# akabeacon_circle_ble113.net
KiCad netlist of a schematic drawn in EAGLE
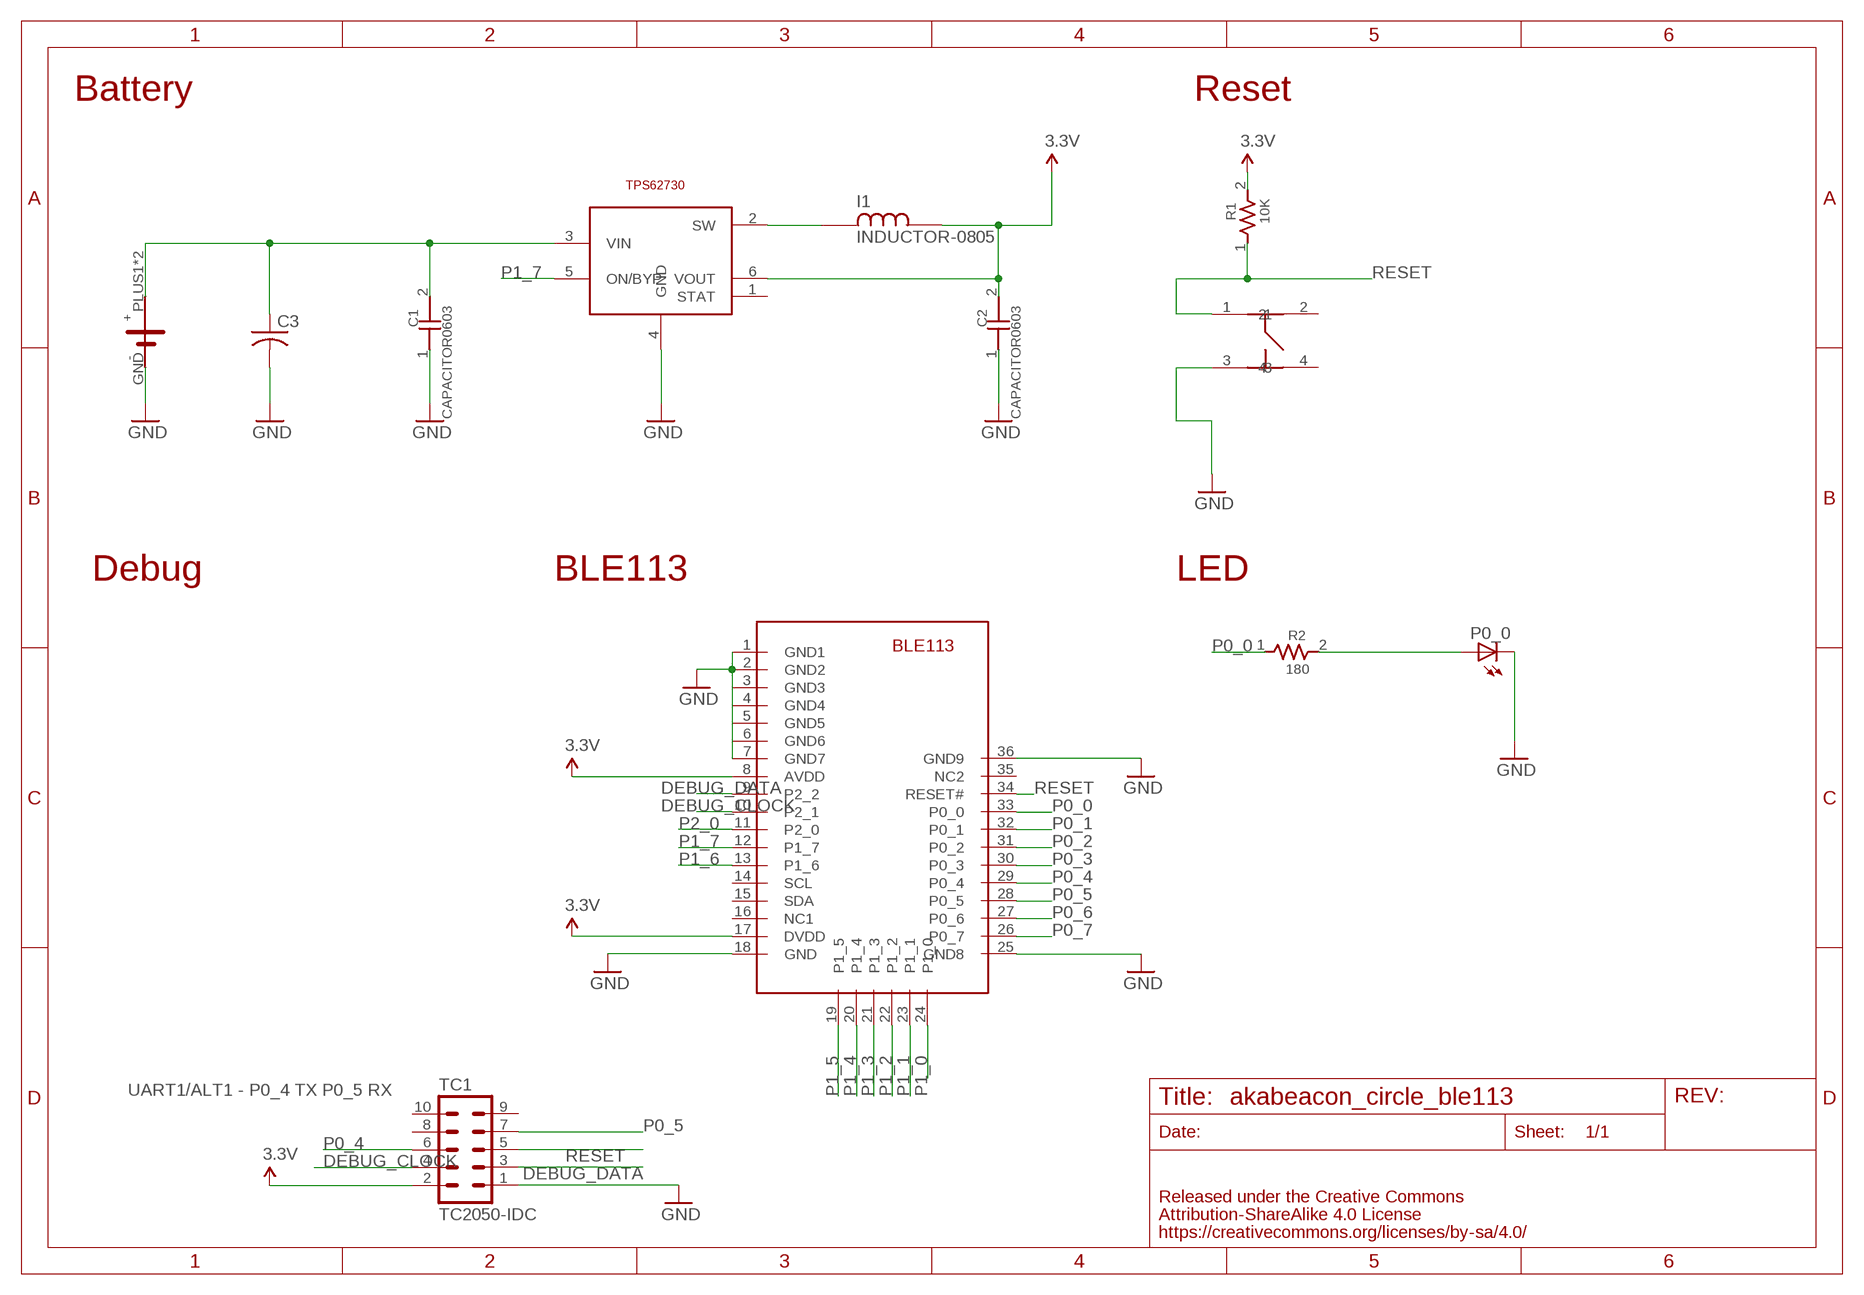
[diagram p0: schematic, sheet 1]

(export (version "E")
  (design (tool "Eeschema 10.0.6"))
  (components
    (comp (ref "C1")
      (value "CAPACITOR0603")
      (footprint "eagle-import:0603")
      (libsource (lib "eagle-import") (part "CAPACITOR0603"))
    )
    (comp (ref "C2")
      (value "CAPACITOR0603")
      (footprint "eagle-import:0603")
      (libsource (lib "eagle-import") (part "CAPACITOR0603"))
    )
    (comp (ref "C3")
      (value "C-USC3225")
      (footprint "eagle-import:C3225")
      (libsource (lib "eagle-import") (part "C-USC3225"))
    )
    (comp (ref "I1")
      (value "INDUCTOR-0805")
      (footprint "eagle-import:INDUCTOR-0805")
      (libsource (lib "eagle-import") (part "INDUCTOR-0805"))
    )
    (comp (ref "P0_0")
      (value "LEDCHIP-LED0603")
      (footprint "eagle-import:CHIP-LED0603")
      (libsource (lib "eagle-import") (part "LEDCHIP-LED0603"))
    )
    (comp (ref "R1")
      (value "10K")
      (footprint "eagle-import:0603")
      (libsource (lib "eagle-import") (part "RESISTOR0603"))
    )
    (comp (ref "R2")
      (value "180")
      (footprint "eagle-import:0603")
      (libsource (lib "eagle-import") (part "RESISTOR0603"))
    )
    (comp (ref "TC1")
      (value "TC2050-IDC")
      (footprint "eagle-import:TC2050-IDC-NL")
      (libsource (lib "eagle-import") (part "TC2050-IDC"))
    )
    (comp (ref "TPS1")
      (value "TI-TPS62730")
      (footprint "eagle-import:TI-TPS62730")
      (libsource (lib "eagle-import") (part "TI-TPS62730"))
    )
    (comp (ref "U$1")
      (value "CIRCLE-TYPE1")
      (footprint "eagle-import:CIRCLE-TYE1-TC2030")
      (libsource (lib "eagle-import") (part "CIRCLE-TYPE1"))
    )
    (comp (ref "U$4")
      (value "BLE113")
      (footprint "eagle-import:BLE113")
      (libsource (lib "eagle-import") (part "BLE113"))
    )
    (comp (ref "U$5")
      (value "SWICTH-4P(KMR2)")
      (footprint "eagle-import:SWITCH-4P(KMR2)")
      (libsource (lib "eagle-import") (part "SWICTH-4P(KMR2)"))
    )
  )
  (nets
    (net (code "1") (name "/DEBUG_CLOCK") (class "Default")
      (node (ref "TC1") (pin "4") (pinfunction "4_4") (pintype "passive"))
      (node (ref "U$4") (pin "10") (pinfunction "P2_1_10") (pintype "bidirectional"))
    )
    (net (code "2") (name "/DEBUG_DATA") (class "Default")
      (node (ref "TC1") (pin "3") (pinfunction "3_3") (pintype "passive"))
      (node (ref "U$4") (pin "9") (pinfunction "P2_2_9") (pintype "bidirectional"))
    )
    (net (code "3") (name "/P0_0") (class "Default")
      (node (ref "R2") (pin "1") (pinfunction "1_1") (pintype "passive"))
      (node (ref "U$4") (pin "33") (pinfunction "P0_0_33") (pintype "bidirectional"))
    )
    (net (code "4") (name "/P0_1") (class "Default")
      (node (ref "U$4") (pin "32") (pinfunction "P0_1_32") (pintype "bidirectional"))
    )
    (net (code "5") (name "/P0_2") (class "Default")
      (node (ref "U$4") (pin "31") (pinfunction "P0_2_31") (pintype "bidirectional"))
    )
    (net (code "6") (name "/P0_3") (class "Default")
      (node (ref "U$4") (pin "30") (pinfunction "P0_3_30") (pintype "bidirectional"))
    )
    (net (code "7") (name "/P0_4") (class "Default")
      (node (ref "TC1") (pin "6") (pinfunction "6_6") (pintype "passive"))
      (node (ref "U$4") (pin "29") (pinfunction "P0_4_29") (pintype "bidirectional"))
    )
    (net (code "8") (name "/P0_5") (class "Default")
      (node (ref "TC1") (pin "7") (pinfunction "7_7") (pintype "passive"))
      (node (ref "U$4") (pin "28") (pinfunction "P0_5_28") (pintype "bidirectional"))
    )
    (net (code "9") (name "/P0_6") (class "Default")
      (node (ref "U$4") (pin "27") (pinfunction "P0_6_27") (pintype "bidirectional"))
    )
    (net (code "10") (name "/P0_7") (class "Default")
      (node (ref "U$4") (pin "26") (pinfunction "P0_7_26") (pintype "bidirectional"))
    )
    (net (code "11") (name "/P1_0") (class "Default")
      (node (ref "U$4") (pin "24") (pinfunction "P1_0_24") (pintype "bidirectional"))
    )
    (net (code "12") (name "/P1_1") (class "Default")
      (node (ref "U$4") (pin "23") (pinfunction "P1_1_23") (pintype "bidirectional"))
    )
    (net (code "13") (name "/P1_2") (class "Default")
      (node (ref "U$4") (pin "22") (pinfunction "P1_2_22") (pintype "bidirectional"))
    )
    (net (code "14") (name "/P1_3") (class "Default")
      (node (ref "U$4") (pin "21") (pinfunction "P1_3_21") (pintype "bidirectional"))
    )
    (net (code "15") (name "/P1_4") (class "Default")
      (node (ref "U$4") (pin "20") (pinfunction "P1_4_20") (pintype "bidirectional"))
    )
    (net (code "16") (name "/P1_5") (class "Default")
      (node (ref "U$4") (pin "19") (pinfunction "P1_5_19") (pintype "bidirectional"))
    )
    (net (code "17") (name "/P1_6") (class "Default")
      (node (ref "U$4") (pin "13") (pinfunction "P1_6_13") (pintype "bidirectional"))
    )
    (net (code "18") (name "/P1_7") (class "Default")
      (node (ref "TPS1") (pin "5") (pinfunction "ON/BYP_5") (pintype "bidirectional"))
      (node (ref "U$4") (pin "12") (pinfunction "P1_7_12") (pintype "bidirectional"))
    )
    (net (code "19") (name "/P2_0") (class "Default")
      (node (ref "U$4") (pin "11") (pinfunction "P2_0_11") (pintype "bidirectional"))
    )
    (net (code "20") (name "/RESET") (class "Default")
      (node (ref "R1") (pin "1") (pinfunction "1_1") (pintype "passive"))
      (node (ref "TC1") (pin "5") (pinfunction "5_5") (pintype "passive"))
      (node (ref "U$4") (pin "34") (pinfunction "RESET#_34") (pintype "bidirectional"))
      (node (ref "U$5") (pin "1") (pinfunction "1_1") (pintype "bidirectional"))
    )
    (net (code "21") (name "3.3V") (class "Default")
      (node (ref "C2") (pin "2") (pinfunction "2_2") (pintype "passive"))
      (node (ref "I1") (pin "P$2") (pinfunction "P$2_P$2") (pintype "bidirectional"))
      (node (ref "R1") (pin "2") (pinfunction "2_2") (pintype "passive"))
      (node (ref "TC1") (pin "2") (pinfunction "2_2") (pintype "passive"))
      (node (ref "TPS1") (pin "6") (pinfunction "VOUT_6") (pintype "bidirectional"))
      (node (ref "U$4") (pin "17") (pinfunction "DVDD_17") (pintype "bidirectional"))
      (node (ref "U$4") (pin "8") (pinfunction "AVDD_8") (pintype "bidirectional"))
    )
    (net (code "22") (name "GND") (class "Default")
      (node (ref "C1") (pin "1") (pinfunction "1_1") (pintype "passive"))
      (node (ref "C2") (pin "1") (pinfunction "1_1") (pintype "passive"))
      (node (ref "C3") (pin "2") (pinfunction "2_2") (pintype "passive"))
      (node (ref "P0_0") (pin "C") (pinfunction "C_C") (pintype "passive"))
      (node (ref "TC1") (pin "1") (pinfunction "1_1") (pintype "passive"))
      (node (ref "TPS1") (pin "4") (pinfunction "GND_4") (pintype "bidirectional"))
      (node (ref "U$1") (pin "GND") (pinfunction "GND_GND") (pintype "bidirectional"))
      (node (ref "U$4") (pin "1") (pinfunction "GND1_1") (pintype "bidirectional"))
      (node (ref "U$4") (pin "18") (pinfunction "GND_18") (pintype "bidirectional"))
      (node (ref "U$4") (pin "2") (pinfunction "GND2_2") (pintype "bidirectional"))
      (node (ref "U$4") (pin "25") (pinfunction "GND8_25") (pintype "bidirectional"))
      (node (ref "U$4") (pin "3") (pinfunction "GND3_3") (pintype "bidirectional"))
      (node (ref "U$4") (pin "36") (pinfunction "GND9_36") (pintype "bidirectional"))
      (node (ref "U$4") (pin "4") (pinfunction "GND4_4") (pintype "bidirectional"))
      (node (ref "U$4") (pin "5") (pinfunction "GND5_5") (pintype "bidirectional"))
      (node (ref "U$4") (pin "6") (pinfunction "GND6_6") (pintype "bidirectional"))
      (node (ref "U$4") (pin "7") (pinfunction "GND7_7") (pintype "bidirectional"))
      (node (ref "U$5") (pin "3") (pinfunction "3_3") (pintype "bidirectional"))
    )
    (net (code "23") (name "Net-(P0_0-PadA)") (class "Default")
      (node (ref "P0_0") (pin "A") (pinfunction "A_A") (pintype "passive"))
      (node (ref "R2") (pin "2") (pinfunction "2_2") (pintype "passive"))
    )
    (net (code "24") (name "Net-(TPS1-SW)") (class "Default")
      (node (ref "I1") (pin "P$1") (pinfunction "P$1_P$1") (pintype "bidirectional"))
      (node (ref "TPS1") (pin "2") (pinfunction "SW_2") (pintype "bidirectional"))
    )
    (net (code "25") (name "Net-(TPS1-VIN)") (class "Default")
      (node (ref "C1") (pin "2") (pinfunction "2_2") (pintype "passive"))
      (node (ref "C3") (pin "1") (pinfunction "1_1") (pintype "passive"))
      (node (ref "TPS1") (pin "3") (pinfunction "VIN_3") (pintype "bidirectional"))
      (node (ref "U$1") (pin "PLUS1") (pinfunction "VCC_PLUS1") (pintype "bidirectional"))
      (node (ref "U$1") (pin "PLUS2") (pinfunction "VCC_PLUS2") (pintype "bidirectional"))
    )
    (net (code "26") (name "unconnected-(TC1-Pad8)") (class "Default")
      (node (ref "TC1") (pin "8") (pinfunction "8_8") (pintype "passive"))
    )
    (net (code "27") (name "unconnected-(TC1-Pad9)") (class "Default")
      (node (ref "TC1") (pin "9") (pinfunction "9_9") (pintype "passive"))
    )
    (net (code "28") (name "unconnected-(TC1-Pad10)") (class "Default")
      (node (ref "TC1") (pin "10") (pinfunction "10_10") (pintype "passive"))
    )
    (net (code "29") (name "unconnected-(TPS1-STAT-Pad1)") (class "Default")
      (node (ref "TPS1") (pin "1") (pinfunction "STAT_1") (pintype "bidirectional"))
    )
    (net (code "30") (name "unconnected-(U$4-NC1-Pad16)") (class "Default")
      (node (ref "U$4") (pin "16") (pinfunction "NC1_16") (pintype "bidirectional"))
    )
    (net (code "31") (name "unconnected-(U$4-NC2-Pad35)") (class "Default")
      (node (ref "U$4") (pin "35") (pinfunction "NC2_35") (pintype "bidirectional"))
    )
    (net (code "32") (name "unconnected-(U$4-SCL-Pad14)") (class "Default")
      (node (ref "U$4") (pin "14") (pinfunction "SCL_14") (pintype "bidirectional"))
    )
    (net (code "33") (name "unconnected-(U$4-SDA-Pad15)") (class "Default")
      (node (ref "U$4") (pin "15") (pinfunction "SDA_15") (pintype "bidirectional"))
    )
    (net (code "34") (name "unconnected-(U$5-Pad2)") (class "Default")
      (node (ref "U$5") (pin "2") (pinfunction "2_2") (pintype "bidirectional"))
    )
    (net (code "35") (name "unconnected-(U$5-Pad4)") (class "Default")
      (node (ref "U$5") (pin "4") (pinfunction "4_4") (pintype "bidirectional"))
    )
  )
)
